# B138B.net
KiCad netlist of a schematic drawn in EAGLE
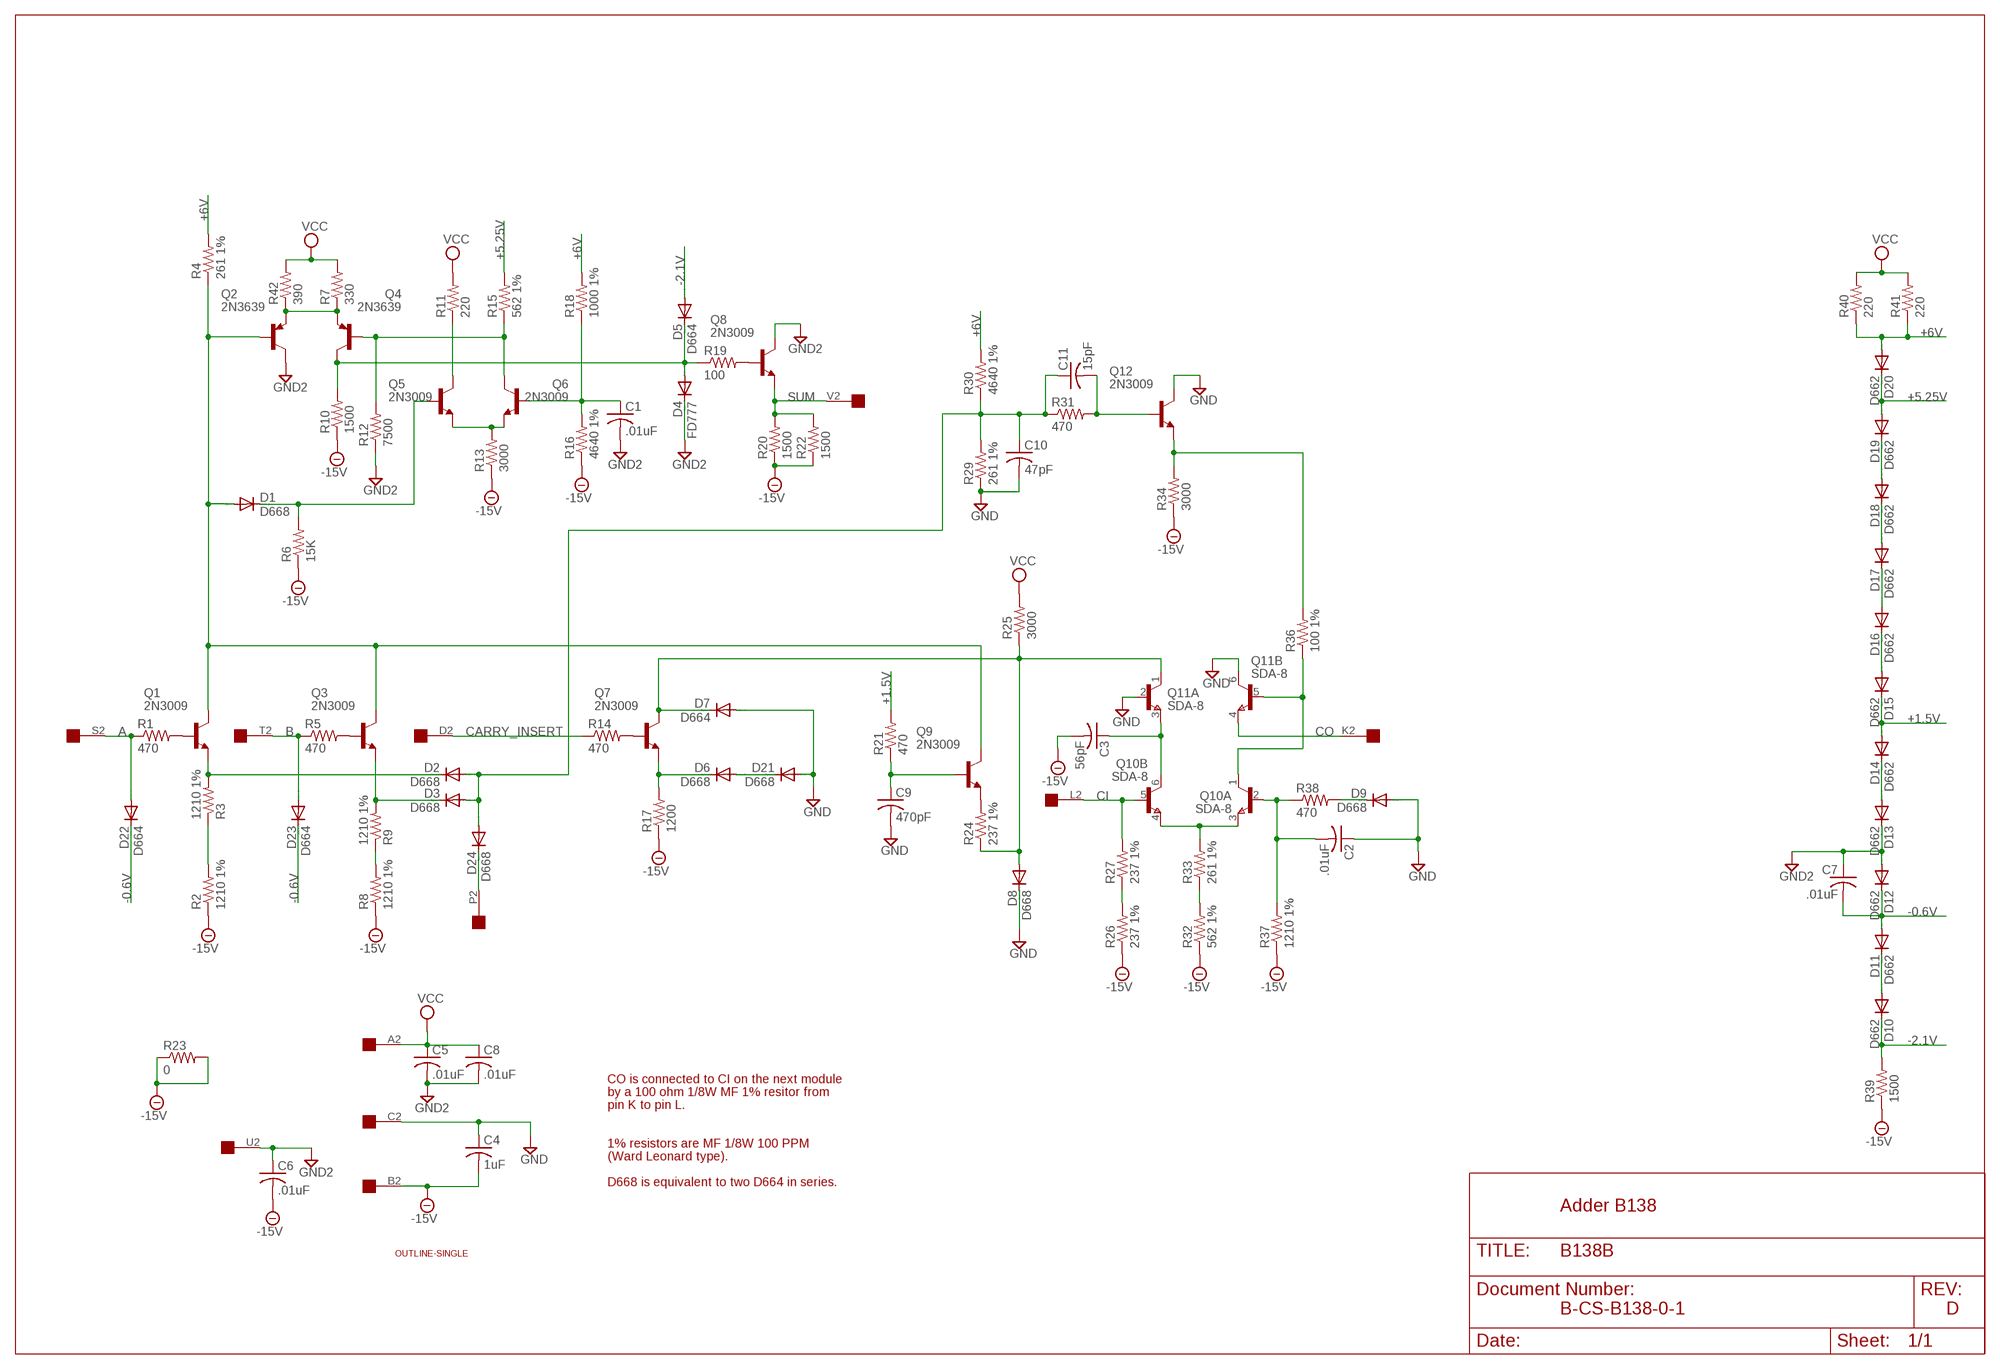
[diagram p0: schematic, sheet 1]

(export (version "E")
  (design (tool "Eeschema 10.0.6"))
  (components
    (comp (ref "C1")
      (value ".01uF")
      (footprint "eagle-import:C063-025X075")
      (libsource (lib "eagle-import") (part "C-US"))
    )
    (comp (ref "C2")
      (value ".01uF")
      (footprint "eagle-import:C063-025X075")
      (libsource (lib "eagle-import") (part "C-US"))
    )
    (comp (ref "C3")
      (value "56pF")
      (footprint "eagle-import:C063-025X075")
      (libsource (lib "eagle-import") (part "C-US"))
    )
    (comp (ref "C4")
      (value "1uF")
      (footprint "eagle-import:C102-043X133")
      (libsource (lib "eagle-import") (part "C-US102-043X133"))
    )
    (comp (ref "C5")
      (value ".01uF")
      (footprint "eagle-import:C063-025X075")
      (libsource (lib "eagle-import") (part "C-US"))
    )
    (comp (ref "C6")
      (value ".01uF")
      (footprint "eagle-import:C063-025X075")
      (libsource (lib "eagle-import") (part "C-US"))
    )
    (comp (ref "C7")
      (value ".01uF")
      (footprint "eagle-import:C063-025X075")
      (libsource (lib "eagle-import") (part "C-US"))
    )
    (comp (ref "C8")
      (value ".01uF")
      (footprint "eagle-import:C063-025X075")
      (libsource (lib "eagle-import") (part "C-US"))
    )
    (comp (ref "C9")
      (value "470pF")
      (footprint "eagle-import:C063-025X075")
      (libsource (lib "eagle-import") (part "C-US"))
    )
    (comp (ref "C10")
      (value "47pF")
      (footprint "eagle-import:C063-025X075")
      (libsource (lib "eagle-import") (part "C-US"))
    )
    (comp (ref "C11")
      (value "15pF")
      (footprint "eagle-import:C063-025X075")
      (libsource (lib "eagle-import") (part "C-US"))
    )
    (comp (ref "D1")
      (value "D668")
      (footprint "eagle-import:DO35-10")
      (libsource (lib "eagle-import") (part "DIODE-DO35-10"))
    )
    (comp (ref "D2")
      (value "D668")
      (footprint "eagle-import:DO35-10")
      (libsource (lib "eagle-import") (part "DIODE-DO35-10"))
    )
    (comp (ref "D3")
      (value "D668")
      (footprint "eagle-import:DO35-10")
      (libsource (lib "eagle-import") (part "DIODE-DO35-10"))
    )
    (comp (ref "D4")
      (value "FD777")
      (footprint "eagle-import:DO35-10")
      (libsource (lib "eagle-import") (part "DIODE-DO35-10"))
    )
    (comp (ref "D5")
      (value "D664")
      (footprint "eagle-import:DO35-10")
      (libsource (lib "eagle-import") (part "DIODE-DO35-10"))
    )
    (comp (ref "D6")
      (value "D668")
      (footprint "eagle-import:DO35-10")
      (libsource (lib "eagle-import") (part "DIODE-DO35-10"))
    )
    (comp (ref "D7")
      (value "D664")
      (footprint "eagle-import:DO35-10")
      (libsource (lib "eagle-import") (part "DIODE-DO35-10"))
    )
    (comp (ref "D8")
      (value "D668")
      (footprint "eagle-import:DO35-10")
      (libsource (lib "eagle-import") (part "DIODE-DO35-10"))
    )
    (comp (ref "D9")
      (value "D668")
      (footprint "eagle-import:DO35-10")
      (libsource (lib "eagle-import") (part "DIODE-DO35-10"))
    )
    (comp (ref "D10")
      (value "D662")
      (footprint "eagle-import:DO35-10")
      (libsource (lib "eagle-import") (part "DIODE-DO35-10"))
    )
    (comp (ref "D11")
      (value "D662")
      (footprint "eagle-import:DO35-10")
      (libsource (lib "eagle-import") (part "DIODE-DO35-10"))
    )
    (comp (ref "D12")
      (value "D662")
      (footprint "eagle-import:DO35-10")
      (libsource (lib "eagle-import") (part "DIODE-DO35-10"))
    )
    (comp (ref "D13")
      (value "D662")
      (footprint "eagle-import:DO35-10")
      (libsource (lib "eagle-import") (part "DIODE-DO35-10"))
    )
    (comp (ref "D14")
      (value "D662")
      (footprint "eagle-import:DO35-10")
      (libsource (lib "eagle-import") (part "DIODE-DO35-10"))
    )
    (comp (ref "D15")
      (value "D662")
      (footprint "eagle-import:DO35-10")
      (libsource (lib "eagle-import") (part "DIODE-DO35-10"))
    )
    (comp (ref "D16")
      (value "D662")
      (footprint "eagle-import:DO35-10")
      (libsource (lib "eagle-import") (part "DIODE-DO35-10"))
    )
    (comp (ref "D17")
      (value "D662")
      (footprint "eagle-import:DO35-10")
      (libsource (lib "eagle-import") (part "DIODE-DO35-10"))
    )
    (comp (ref "D18")
      (value "D662")
      (footprint "eagle-import:DO35-10")
      (libsource (lib "eagle-import") (part "DIODE-DO35-10"))
    )
    (comp (ref "D19")
      (value "D662")
      (footprint "eagle-import:DO35-10")
      (libsource (lib "eagle-import") (part "DIODE-DO35-10"))
    )
    (comp (ref "D20")
      (value "D662")
      (footprint "eagle-import:DO35-10")
      (libsource (lib "eagle-import") (part "DIODE-DO35-10"))
    )
    (comp (ref "D21")
      (value "D668")
      (footprint "eagle-import:DO35-10")
      (libsource (lib "eagle-import") (part "DIODE-DO35-10"))
    )
    (comp (ref "D22")
      (value "D664")
      (footprint "eagle-import:DO35-10")
      (libsource (lib "eagle-import") (part "DIODE-DO35-10"))
    )
    (comp (ref "D23")
      (value "D664")
      (footprint "eagle-import:DO35-10")
      (libsource (lib "eagle-import") (part "DIODE-DO35-10"))
    )
    (comp (ref "D24")
      (value "D668")
      (footprint "eagle-import:DO35-10")
      (libsource (lib "eagle-import") (part "DIODE-DO35-10"))
    )
    (comp (ref "Q1")
      (value "2N3009")
      (footprint "eagle-import:TO5")
      (libsource (lib "eagle-import") (part "-NPN-TO5"))
    )
    (comp (ref "Q2")
      (value "2N3639")
      (footprint "eagle-import:TO5")
      (libsource (lib "eagle-import") (part "-PNP-TO5"))
    )
    (comp (ref "Q3")
      (value "2N3009")
      (footprint "eagle-import:TO5")
      (libsource (lib "eagle-import") (part "-NPN-TO5"))
    )
    (comp (ref "Q4")
      (value "2N3639")
      (footprint "eagle-import:TO5")
      (libsource (lib "eagle-import") (part "-PNP-TO5"))
    )
    (comp (ref "Q5")
      (value "2N3009")
      (footprint "eagle-import:TO5")
      (libsource (lib "eagle-import") (part "-NPN-TO5"))
    )
    (comp (ref "Q6")
      (value "2N3009")
      (footprint "eagle-import:TO5")
      (libsource (lib "eagle-import") (part "-NPN-TO5"))
    )
    (comp (ref "Q7")
      (value "2N3009")
      (footprint "eagle-import:TO5")
      (libsource (lib "eagle-import") (part "-NPN-TO5"))
    )
    (comp (ref "Q8")
      (value "2N3009")
      (footprint "eagle-import:TO5")
      (libsource (lib "eagle-import") (part "-NPN-TO5"))
    )
    (comp (ref "Q9")
      (value "2N3009")
      (footprint "eagle-import:TO5")
      (libsource (lib "eagle-import") (part "-NPN-TO5"))
    )
    (comp (ref "Q10")
      (value "SDA-8")
      (footprint "eagle-import:TO78")
      (libsource (lib "eagle-import") (part "MAT-02H"))
    )
    (comp (ref "Q11")
      (value "SDA-8")
      (footprint "eagle-import:TO78")
      (libsource (lib "eagle-import") (part "MAT-02H"))
    )
    (comp (ref "Q12")
      (value "2N3009")
      (footprint "eagle-import:TO5")
      (libsource (lib "eagle-import") (part "-NPN-TO5"))
    )
    (comp (ref "R1")
      (value "470")
      (footprint "eagle-import:0207_10")
      (libsource (lib "eagle-import") (part "R-US_0207/10"))
    )
    (comp (ref "R2")
      (value "1210 1%")
      (footprint "eagle-import:0207_15")
      (libsource (lib "eagle-import") (part "R-US_0207/15"))
    )
    (comp (ref "R3")
      (value "1210 1%")
      (footprint "eagle-import:0207_15")
      (libsource (lib "eagle-import") (part "R-US_0207/15"))
    )
    (comp (ref "R4")
      (value "261 1%")
      (footprint "eagle-import:0207_15")
      (libsource (lib "eagle-import") (part "R-US_0207/15"))
    )
    (comp (ref "R5")
      (value "470")
      (footprint "eagle-import:0207_10")
      (libsource (lib "eagle-import") (part "R-US_0207/10"))
    )
    (comp (ref "R6")
      (value "15K")
      (footprint "eagle-import:0207_10")
      (libsource (lib "eagle-import") (part "R-US_0207/10"))
    )
    (comp (ref "R7")
      (value "330")
      (footprint "eagle-import:0207_10")
      (libsource (lib "eagle-import") (part "R-US_0207/10"))
    )
    (comp (ref "R8")
      (value "1210 1%")
      (footprint "eagle-import:0207_15")
      (libsource (lib "eagle-import") (part "R-US_0207/15"))
    )
    (comp (ref "R9")
      (value "1210 1%")
      (footprint "eagle-import:0207_15")
      (libsource (lib "eagle-import") (part "R-US_0207/15"))
    )
    (comp (ref "R10")
      (value "1500")
      (footprint "eagle-import:0207_10")
      (libsource (lib "eagle-import") (part "R-US_0207/10"))
    )
    (comp (ref "R11")
      (value "220")
      (footprint "eagle-import:0207_10")
      (libsource (lib "eagle-import") (part "R-US_0207/10"))
    )
    (comp (ref "R12")
      (value "7500")
      (footprint "eagle-import:0207_10")
      (libsource (lib "eagle-import") (part "R-US_0207/10"))
    )
    (comp (ref "R13")
      (value "3000")
      (footprint "eagle-import:0207_10")
      (libsource (lib "eagle-import") (part "R-US_0207/10"))
    )
    (comp (ref "R14")
      (value "470")
      (footprint "eagle-import:0207_10")
      (libsource (lib "eagle-import") (part "R-US_0207/10"))
    )
    (comp (ref "R15")
      (value "562 1%")
      (footprint "eagle-import:0207_15")
      (libsource (lib "eagle-import") (part "R-US_0207/15"))
    )
    (comp (ref "R16")
      (value "4640 1%")
      (footprint "eagle-import:0207_15")
      (libsource (lib "eagle-import") (part "R-US_0207/15"))
    )
    (comp (ref "R17")
      (value "1200")
      (footprint "eagle-import:0207_10")
      (libsource (lib "eagle-import") (part "R-US_0207/10"))
    )
    (comp (ref "R18")
      (value "1000 1%")
      (footprint "eagle-import:0207_15")
      (libsource (lib "eagle-import") (part "R-US_0207/15"))
    )
    (comp (ref "R19")
      (value "100")
      (footprint "eagle-import:0207_10")
      (libsource (lib "eagle-import") (part "R-US_0207/10"))
    )
    (comp (ref "R20")
      (value "1500")
      (footprint "eagle-import:0207_10")
      (libsource (lib "eagle-import") (part "R-US_0207/10"))
    )
    (comp (ref "R21")
      (value "470")
      (footprint "eagle-import:0207_10")
      (libsource (lib "eagle-import") (part "R-US_0207/10"))
    )
    (comp (ref "R22")
      (value "1500")
      (footprint "eagle-import:0207_10")
      (libsource (lib "eagle-import") (part "R-US_0207/10"))
    )
    (comp (ref "R23")
      (value "0")
      (footprint "eagle-import:0207_10")
      (libsource (lib "eagle-import") (part "R-US_0207/10"))
    )
    (comp (ref "R24")
      (value "237 1%")
      (footprint "eagle-import:0207_15")
      (libsource (lib "eagle-import") (part "R-US_0207/15"))
    )
    (comp (ref "R25")
      (value "3000")
      (footprint "eagle-import:0207_10")
      (libsource (lib "eagle-import") (part "R-US_0207/10"))
    )
    (comp (ref "R26")
      (value "237 1%")
      (footprint "eagle-import:0207_15")
      (libsource (lib "eagle-import") (part "R-US_0207/15"))
    )
    (comp (ref "R27")
      (value "237 1%")
      (footprint "eagle-import:0207_15")
      (libsource (lib "eagle-import") (part "R-US_0207/15"))
    )
    (comp (ref "R29")
      (value "261 1%")
      (footprint "eagle-import:0207_15")
      (libsource (lib "eagle-import") (part "R-US_0207/15"))
    )
    (comp (ref "R30")
      (value "4640 1%")
      (footprint "eagle-import:0207_15")
      (libsource (lib "eagle-import") (part "R-US_0207/15"))
    )
    (comp (ref "R31")
      (value "470")
      (footprint "eagle-import:0207_10")
      (libsource (lib "eagle-import") (part "R-US_0207/10"))
    )
    (comp (ref "R32")
      (value "562 1%")
      (footprint "eagle-import:0207_15")
      (libsource (lib "eagle-import") (part "R-US_0207/15"))
    )
    (comp (ref "R33")
      (value "261 1%")
      (footprint "eagle-import:0207_15")
      (libsource (lib "eagle-import") (part "R-US_0207/15"))
    )
    (comp (ref "R34")
      (value "3000")
      (footprint "eagle-import:0207_10")
      (libsource (lib "eagle-import") (part "R-US_0207/10"))
    )
    (comp (ref "R36")
      (value "100 1%")
      (footprint "eagle-import:0207_15")
      (libsource (lib "eagle-import") (part "R-US_0207/15"))
    )
    (comp (ref "R37")
      (value "1210 1%")
      (footprint "eagle-import:0207_15")
      (libsource (lib "eagle-import") (part "R-US_0207/15"))
    )
    (comp (ref "R38")
      (value "470")
      (footprint "eagle-import:0207_10")
      (libsource (lib "eagle-import") (part "R-US_0207/10"))
    )
    (comp (ref "R39")
      (value "1500")
      (footprint "eagle-import:0207_10")
      (libsource (lib "eagle-import") (part "R-US_0207/10"))
    )
    (comp (ref "R40")
      (value "220")
      (footprint "eagle-import:0207_10")
      (libsource (lib "eagle-import") (part "R-US_0207/10"))
    )
    (comp (ref "R41")
      (value "220")
      (footprint "eagle-import:0207_10")
      (libsource (lib "eagle-import") (part "R-US_0207/10"))
    )
    (comp (ref "R42")
      (value "390")
      (footprint "eagle-import:0207_10")
      (libsource (lib "eagle-import") (part "R-US_0207/10"))
    )
    (comp (ref "U$1")
      (value "OUTLINE-SINGLE")
      (footprint "eagle-import:SINGLE")
      (libsource (lib "eagle-import") (part "OUTLINE-SINGLE"))
    )
    (comp (ref "U$2")
      (value "EDGE-1")
      (footprint "eagle-import:EDGE-CON1")
      (libsource (lib "eagle-import") (part "EDGE-1"))
    )
  )
  (nets
    (net (code "1") (name "-15V") (class "Default")
      (node (ref "C3") (pin "2") (pinfunction "2_2") (pintype "passive"))
      (node (ref "C4") (pin "2") (pinfunction "2_2") (pintype "passive"))
      (node (ref "C6") (pin "2") (pinfunction "2_2") (pintype "passive"))
      (node (ref "R10") (pin "1") (pinfunction "1_1") (pintype "passive"))
      (node (ref "R13") (pin "1") (pinfunction "1_1") (pintype "passive"))
      (node (ref "R16") (pin "1") (pinfunction "1_1") (pintype "passive"))
      (node (ref "R17") (pin "1") (pinfunction "1_1") (pintype "passive"))
      (node (ref "R2") (pin "1") (pinfunction "1_1") (pintype "passive"))
      (node (ref "R20") (pin "1") (pinfunction "1_1") (pintype "passive"))
      (node (ref "R22") (pin "1") (pinfunction "1_1") (pintype "passive"))
      (node (ref "R23") (pin "1") (pinfunction "1_1") (pintype "passive"))
      (node (ref "R23") (pin "2") (pinfunction "2_2") (pintype "passive"))
      (node (ref "R26") (pin "1") (pinfunction "1_1") (pintype "passive"))
      (node (ref "R32") (pin "1") (pinfunction "1_1") (pintype "passive"))
      (node (ref "R34") (pin "1") (pinfunction "1_1") (pintype "passive"))
      (node (ref "R37") (pin "1") (pinfunction "1_1") (pintype "passive"))
      (node (ref "R39") (pin "1") (pinfunction "1_1") (pintype "passive"))
      (node (ref "R6") (pin "1") (pinfunction "1_1") (pintype "passive"))
      (node (ref "R8") (pin "1") (pinfunction "1_1") (pintype "passive"))
      (node (ref "U$2") (pin "B2") (pinfunction "1_B2") (pintype "bidirectional"))
    )
    (net (code "2") (name "/+1.5V") (class "Default")
      (node (ref "D14") (pin "A") (pinfunction "A_A") (pintype "passive"))
      (node (ref "D15") (pin "C") (pinfunction "C_C") (pintype "passive"))
      (node (ref "R21") (pin "2") (pinfunction "2_2") (pintype "passive"))
    )
    (net (code "3") (name "/+5.25V") (class "Default")
      (node (ref "D19") (pin "A") (pinfunction "A_A") (pintype "passive"))
      (node (ref "D20") (pin "C") (pinfunction "C_C") (pintype "passive"))
      (node (ref "R15") (pin "2") (pinfunction "2_2") (pintype "passive"))
    )
    (net (code "4") (name "/+6V") (class "Default")
      (node (ref "D20") (pin "A") (pinfunction "A_A") (pintype "passive"))
      (node (ref "R18") (pin "2") (pinfunction "2_2") (pintype "passive"))
      (node (ref "R30") (pin "2") (pinfunction "2_2") (pintype "passive"))
      (node (ref "R4") (pin "2") (pinfunction "2_2") (pintype "passive"))
      (node (ref "R40") (pin "1") (pinfunction "1_1") (pintype "passive"))
      (node (ref "R41") (pin "1") (pinfunction "1_1") (pintype "passive"))
    )
    (net (code "5") (name "/-0.6V") (class "Default")
      (node (ref "C7") (pin "2") (pinfunction "2_2") (pintype "passive"))
      (node (ref "D11") (pin "A") (pinfunction "A_A") (pintype "passive"))
      (node (ref "D12") (pin "C") (pinfunction "C_C") (pintype "passive"))
      (node (ref "D22") (pin "C") (pinfunction "C_C") (pintype "passive"))
      (node (ref "D23") (pin "C") (pinfunction "C_C") (pintype "passive"))
    )
    (net (code "6") (name "/-2.1V") (class "Default")
      (node (ref "D10") (pin "C") (pinfunction "C_C") (pintype "passive"))
      (node (ref "D5") (pin "A") (pinfunction "A_A") (pintype "passive"))
      (node (ref "R39") (pin "2") (pinfunction "2_2") (pintype "passive"))
    )
    (net (code "7") (name "/A") (class "Default")
      (node (ref "D22") (pin "A") (pinfunction "A_A") (pintype "passive"))
      (node (ref "R1") (pin "1") (pinfunction "1_1") (pintype "passive"))
      (node (ref "U$2") (pin "S2") (pinfunction "1_S2") (pintype "bidirectional"))
    )
    (net (code "8") (name "/B") (class "Default")
      (node (ref "D23") (pin "A") (pinfunction "A_A") (pintype "passive"))
      (node (ref "R5") (pin "1") (pinfunction "1_1") (pintype "passive"))
      (node (ref "U$2") (pin "T2") (pinfunction "1_T2") (pintype "bidirectional"))
    )
    (net (code "9") (name "/CARRY_INSERT") (class "Default")
      (node (ref "R14") (pin "1") (pinfunction "1_1") (pintype "passive"))
      (node (ref "U$2") (pin "D2") (pinfunction "1_D2") (pintype "bidirectional"))
    )
    (net (code "10") (name "/CI") (class "Default")
      (node (ref "Q10") (pin "5") (pinfunction "B_5") (pintype "passive"))
      (node (ref "R27") (pin "2") (pinfunction "2_2") (pintype "passive"))
      (node (ref "U$2") (pin "L2") (pinfunction "1_L2") (pintype "bidirectional"))
    )
    (net (code "11") (name "/CO") (class "Default")
      (node (ref "Q11") (pin "4") (pinfunction "E_4") (pintype "passive"))
      (node (ref "U$2") (pin "K2") (pinfunction "1_K2") (pintype "bidirectional"))
    )
    (net (code "12") (name "/SUM") (class "Default")
      (node (ref "Q8") (pin "1") (pinfunction "E_1") (pintype "passive"))
      (node (ref "R20") (pin "2") (pinfunction "2_2") (pintype "passive"))
      (node (ref "R22") (pin "2") (pinfunction "2_2") (pintype "passive"))
      (node (ref "U$2") (pin "V2") (pinfunction "1_V2") (pintype "bidirectional"))
    )
    (net (code "13") (name "GND") (class "Default")
      (node (ref "C10") (pin "2") (pinfunction "2_2") (pintype "passive"))
      (node (ref "C2") (pin "1") (pinfunction "1_1") (pintype "passive"))
      (node (ref "C4") (pin "1") (pinfunction "1_1") (pintype "passive"))
      (node (ref "C9") (pin "2") (pinfunction "2_2") (pintype "passive"))
      (node (ref "D21") (pin "A") (pinfunction "A_A") (pintype "passive"))
      (node (ref "D7") (pin "A") (pinfunction "A_A") (pintype "passive"))
      (node (ref "D8") (pin "C") (pinfunction "C_C") (pintype "passive"))
      (node (ref "D9") (pin "A") (pinfunction "A_A") (pintype "passive"))
      (node (ref "Q11") (pin "2") (pinfunction "B_2") (pintype "passive"))
      (node (ref "Q11") (pin "6") (pinfunction "C_6") (pintype "passive"))
      (node (ref "Q12") (pin "3") (pinfunction "C_3") (pintype "passive"))
      (node (ref "R29") (pin "1") (pinfunction "1_1") (pintype "passive"))
      (node (ref "U$2") (pin "C2") (pinfunction "1_C2") (pintype "bidirectional"))
    )
    (net (code "14") (name "GND2") (class "Default")
      (node (ref "C1") (pin "2") (pinfunction "2_2") (pintype "passive"))
      (node (ref "C5") (pin "2") (pinfunction "2_2") (pintype "passive"))
      (node (ref "C6") (pin "1") (pinfunction "1_1") (pintype "passive"))
      (node (ref "C7") (pin "1") (pinfunction "1_1") (pintype "passive"))
      (node (ref "C8") (pin "2") (pinfunction "2_2") (pintype "passive"))
      (node (ref "D12") (pin "A") (pinfunction "A_A") (pintype "passive"))
      (node (ref "D13") (pin "C") (pinfunction "C_C") (pintype "passive"))
      (node (ref "D4") (pin "C") (pinfunction "C_C") (pintype "passive"))
      (node (ref "Q2") (pin "3") (pinfunction "C_3") (pintype "passive"))
      (node (ref "Q8") (pin "3") (pinfunction "C_3") (pintype "passive"))
      (node (ref "R12") (pin "1") (pinfunction "1_1") (pintype "passive"))
      (node (ref "U$2") (pin "U2") (pinfunction "1_U2") (pintype "bidirectional"))
    )
    (net (code "15") (name "Net-(C10-Pad1)") (class "Default")
      (node (ref "C10") (pin "1") (pinfunction "1_1") (pintype "passive"))
      (node (ref "C11") (pin "1") (pinfunction "1_1") (pintype "passive"))
      (node (ref "D2") (pin "A") (pinfunction "A_A") (pintype "passive"))
      (node (ref "D24") (pin "A") (pinfunction "A_A") (pintype "passive"))
      (node (ref "D3") (pin "A") (pinfunction "A_A") (pintype "passive"))
      (node (ref "R29") (pin "2") (pinfunction "2_2") (pintype "passive"))
      (node (ref "R30") (pin "1") (pinfunction "1_1") (pintype "passive"))
      (node (ref "R31") (pin "1") (pinfunction "1_1") (pintype "passive"))
    )
    (net (code "16") (name "Net-(D9-PadC)") (class "Default")
      (node (ref "D9") (pin "C") (pinfunction "C_C") (pintype "passive"))
      (node (ref "R38") (pin "2") (pinfunction "2_2") (pintype "passive"))
    )
    (net (code "17") (name "Net-(D10-PadA)") (class "Default")
      (node (ref "D10") (pin "A") (pinfunction "A_A") (pintype "passive"))
      (node (ref "D11") (pin "C") (pinfunction "C_C") (pintype "passive"))
    )
    (net (code "18") (name "Net-(D13-PadA)") (class "Default")
      (node (ref "D13") (pin "A") (pinfunction "A_A") (pintype "passive"))
      (node (ref "D14") (pin "C") (pinfunction "C_C") (pintype "passive"))
    )
    (net (code "19") (name "Net-(D15-PadA)") (class "Default")
      (node (ref "D15") (pin "A") (pinfunction "A_A") (pintype "passive"))
      (node (ref "D16") (pin "C") (pinfunction "C_C") (pintype "passive"))
    )
    (net (code "20") (name "Net-(D16-PadA)") (class "Default")
      (node (ref "D16") (pin "A") (pinfunction "A_A") (pintype "passive"))
      (node (ref "D17") (pin "C") (pinfunction "C_C") (pintype "passive"))
    )
    (net (code "21") (name "Net-(D17-PadA)") (class "Default")
      (node (ref "D17") (pin "A") (pinfunction "A_A") (pintype "passive"))
      (node (ref "D18") (pin "C") (pinfunction "C_C") (pintype "passive"))
    )
    (net (code "22") (name "Net-(D18-PadA)") (class "Default")
      (node (ref "D18") (pin "A") (pinfunction "A_A") (pintype "passive"))
      (node (ref "D19") (pin "C") (pinfunction "C_C") (pintype "passive"))
    )
    (net (code "23") (name "Net-(D21-PadC)") (class "Default")
      (node (ref "D21") (pin "C") (pinfunction "C_C") (pintype "passive"))
      (node (ref "D6") (pin "A") (pinfunction "A_A") (pintype "passive"))
    )
    (net (code "24") (name "Net-(Q1-B)") (class "Default")
      (node (ref "Q1") (pin "2") (pinfunction "B_2") (pintype "passive"))
      (node (ref "R1") (pin "2") (pinfunction "2_2") (pintype "passive"))
    )
    (net (code "25") (name "Net-(Q1-C)") (class "Default")
      (node (ref "D1") (pin "A") (pinfunction "A_A") (pintype "passive"))
      (node (ref "Q1") (pin "3") (pinfunction "C_3") (pintype "passive"))
      (node (ref "Q2") (pin "2") (pinfunction "B_2") (pintype "passive"))
      (node (ref "Q3") (pin "3") (pinfunction "C_3") (pintype "passive"))
      (node (ref "Q9") (pin "3") (pinfunction "C_3") (pintype "passive"))
      (node (ref "R4") (pin "1") (pinfunction "1_1") (pintype "passive"))
    )
    (net (code "26") (name "Net-(Q1-E)") (class "Default")
      (node (ref "D2") (pin "C") (pinfunction "C_C") (pintype "passive"))
      (node (ref "Q1") (pin "1") (pinfunction "E_1") (pintype "passive"))
      (node (ref "R3") (pin "2") (pinfunction "2_2") (pintype "passive"))
    )
    (net (code "27") (name "Net-(Q2-E)") (class "Default")
      (node (ref "Q2") (pin "1") (pinfunction "E_1") (pintype "passive"))
      (node (ref "Q4") (pin "1") (pinfunction "E_1") (pintype "passive"))
      (node (ref "R42") (pin "1") (pinfunction "1_1") (pintype "passive"))
      (node (ref "R7") (pin "1") (pinfunction "1_1") (pintype "passive"))
    )
    (net (code "28") (name "Net-(Q3-B)") (class "Default")
      (node (ref "Q3") (pin "2") (pinfunction "B_2") (pintype "passive"))
      (node (ref "R5") (pin "2") (pinfunction "2_2") (pintype "passive"))
    )
    (net (code "29") (name "Net-(Q3-E)") (class "Default")
      (node (ref "D3") (pin "C") (pinfunction "C_C") (pintype "passive"))
      (node (ref "Q3") (pin "1") (pinfunction "E_1") (pintype "passive"))
      (node (ref "R9") (pin "2") (pinfunction "2_2") (pintype "passive"))
    )
    (net (code "30") (name "Net-(Q4-B)") (class "Default")
      (node (ref "Q4") (pin "2") (pinfunction "B_2") (pintype "passive"))
      (node (ref "Q6") (pin "3") (pinfunction "C_3") (pintype "passive"))
      (node (ref "R12") (pin "2") (pinfunction "2_2") (pintype "passive"))
      (node (ref "R15") (pin "1") (pinfunction "1_1") (pintype "passive"))
    )
    (net (code "31") (name "Net-(Q4-C)") (class "Default")
      (node (ref "D4") (pin "A") (pinfunction "A_A") (pintype "passive"))
      (node (ref "D5") (pin "C") (pinfunction "C_C") (pintype "passive"))
      (node (ref "Q4") (pin "3") (pinfunction "C_3") (pintype "passive"))
      (node (ref "R10") (pin "2") (pinfunction "2_2") (pintype "passive"))
      (node (ref "R19") (pin "1") (pinfunction "1_1") (pintype "passive"))
    )
    (net (code "32") (name "Net-(Q5-B)") (class "Default")
      (node (ref "D1") (pin "C") (pinfunction "C_C") (pintype "passive"))
      (node (ref "Q5") (pin "2") (pinfunction "B_2") (pintype "passive"))
      (node (ref "R6") (pin "2") (pinfunction "2_2") (pintype "passive"))
    )
    (net (code "33") (name "Net-(Q5-C)") (class "Default")
      (node (ref "Q5") (pin "3") (pinfunction "C_3") (pintype "passive"))
      (node (ref "R11") (pin "1") (pinfunction "1_1") (pintype "passive"))
    )
    (net (code "34") (name "Net-(Q5-E)") (class "Default")
      (node (ref "Q5") (pin "1") (pinfunction "E_1") (pintype "passive"))
      (node (ref "Q6") (pin "1") (pinfunction "E_1") (pintype "passive"))
      (node (ref "R13") (pin "2") (pinfunction "2_2") (pintype "passive"))
    )
    (net (code "35") (name "Net-(Q6-B)") (class "Default")
      (node (ref "C1") (pin "1") (pinfunction "1_1") (pintype "passive"))
      (node (ref "Q6") (pin "2") (pinfunction "B_2") (pintype "passive"))
      (node (ref "R16") (pin "2") (pinfunction "2_2") (pintype "passive"))
      (node (ref "R18") (pin "1") (pinfunction "1_1") (pintype "passive"))
    )
    (net (code "36") (name "Net-(Q7-B)") (class "Default")
      (node (ref "Q7") (pin "2") (pinfunction "B_2") (pintype "passive"))
      (node (ref "R14") (pin "2") (pinfunction "2_2") (pintype "passive"))
    )
    (net (code "37") (name "Net-(Q7-E)") (class "Default")
      (node (ref "D6") (pin "C") (pinfunction "C_C") (pintype "passive"))
      (node (ref "Q7") (pin "1") (pinfunction "E_1") (pintype "passive"))
      (node (ref "R17") (pin "2") (pinfunction "2_2") (pintype "passive"))
    )
    (net (code "38") (name "Net-(Q8-B)") (class "Default")
      (node (ref "Q8") (pin "2") (pinfunction "B_2") (pintype "passive"))
      (node (ref "R19") (pin "2") (pinfunction "2_2") (pintype "passive"))
    )
    (net (code "39") (name "Net-(Q9-B)") (class "Default")
      (node (ref "C9") (pin "1") (pinfunction "1_1") (pintype "passive"))
      (node (ref "Q9") (pin "2") (pinfunction "B_2") (pintype "passive"))
      (node (ref "R21") (pin "1") (pinfunction "1_1") (pintype "passive"))
    )
    (net (code "40") (name "Net-(Q9-E)") (class "Default")
      (node (ref "Q9") (pin "1") (pinfunction "E_1") (pintype "passive"))
      (node (ref "R24") (pin "2") (pinfunction "2_2") (pintype "passive"))
    )
    (net (code "41") (name "Net-(Q10A-B)") (class "Default")
      (node (ref "C2") (pin "2") (pinfunction "2_2") (pintype "passive"))
      (node (ref "Q10") (pin "2") (pinfunction "B_2") (pintype "passive"))
      (node (ref "R37") (pin "2") (pinfunction "2_2") (pintype "passive"))
      (node (ref "R38") (pin "1") (pinfunction "1_1") (pintype "passive"))
    )
    (net (code "42") (name "Net-(Q10A-C)") (class "Default")
      (node (ref "Q10") (pin "1") (pinfunction "C_1") (pintype "passive"))
      (node (ref "Q11") (pin "5") (pinfunction "B_5") (pintype "passive"))
      (node (ref "R36") (pin "1") (pinfunction "1_1") (pintype "passive"))
    )
    (net (code "43") (name "Net-(Q10A-E)") (class "Default")
      (node (ref "Q10") (pin "3") (pinfunction "E_3") (pintype "passive"))
      (node (ref "Q10") (pin "4") (pinfunction "E_4") (pintype "passive"))
      (node (ref "R33") (pin "2") (pinfunction "2_2") (pintype "passive"))
    )
    (net (code "44") (name "Net-(Q10B-C)") (class "Default")
      (node (ref "C3") (pin "1") (pinfunction "1_1") (pintype "passive"))
      (node (ref "Q10") (pin "6") (pinfunction "C_6") (pintype "passive"))
      (node (ref "Q11") (pin "3") (pinfunction "E_3") (pintype "passive"))
    )
    (net (code "45") (name "Net-(Q11A-C)") (class "Default")
      (node (ref "D7") (pin "C") (pinfunction "C_C") (pintype "passive"))
      (node (ref "D8") (pin "A") (pinfunction "A_A") (pintype "passive"))
      (node (ref "Q11") (pin "1") (pinfunction "C_1") (pintype "passive"))
      (node (ref "Q7") (pin "3") (pinfunction "C_3") (pintype "passive"))
      (node (ref "R24") (pin "1") (pinfunction "1_1") (pintype "passive"))
      (node (ref "R25") (pin "1") (pinfunction "1_1") (pintype "passive"))
    )
    (net (code "46") (name "Net-(Q12-B)") (class "Default")
      (node (ref "C11") (pin "2") (pinfunction "2_2") (pintype "passive"))
      (node (ref "Q12") (pin "2") (pinfunction "B_2") (pintype "passive"))
      (node (ref "R31") (pin "2") (pinfunction "2_2") (pintype "passive"))
    )
    (net (code "47") (name "Net-(Q12-E)") (class "Default")
      (node (ref "Q12") (pin "1") (pinfunction "E_1") (pintype "passive"))
      (node (ref "R34") (pin "2") (pinfunction "2_2") (pintype "passive"))
      (node (ref "R36") (pin "2") (pinfunction "2_2") (pintype "passive"))
    )
    (net (code "48") (name "Net-(R2-Pad2)") (class "Default")
      (node (ref "R2") (pin "2") (pinfunction "2_2") (pintype "passive"))
      (node (ref "R3") (pin "1") (pinfunction "1_1") (pintype "passive"))
    )
    (net (code "49") (name "Net-(R8-Pad2)") (class "Default")
      (node (ref "R8") (pin "2") (pinfunction "2_2") (pintype "passive"))
      (node (ref "R9") (pin "1") (pinfunction "1_1") (pintype "passive"))
    )
    (net (code "50") (name "Net-(R26-Pad2)") (class "Default")
      (node (ref "R26") (pin "2") (pinfunction "2_2") (pintype "passive"))
      (node (ref "R27") (pin "1") (pinfunction "1_1") (pintype "passive"))
    )
    (net (code "51") (name "Net-(R32-Pad2)") (class "Default")
      (node (ref "R32") (pin "2") (pinfunction "2_2") (pintype "passive"))
      (node (ref "R33") (pin "1") (pinfunction "1_1") (pintype "passive"))
    )
    (net (code "52") (name "Net-(U$2M-1)") (class "Default")
      (node (ref "D24") (pin "C") (pinfunction "C_C") (pintype "passive"))
      (node (ref "U$2") (pin "P2") (pinfunction "1_P2") (pintype "bidirectional"))
    )
    (net (code "53") (name "VCC") (class "Default")
      (node (ref "C5") (pin "1") (pinfunction "1_1") (pintype "passive"))
      (node (ref "C8") (pin "1") (pinfunction "1_1") (pintype "passive"))
      (node (ref "R11") (pin "2") (pinfunction "2_2") (pintype "passive"))
      (node (ref "R25") (pin "2") (pinfunction "2_2") (pintype "passive"))
      (node (ref "R40") (pin "2") (pinfunction "2_2") (pintype "passive"))
      (node (ref "R41") (pin "2") (pinfunction "2_2") (pintype "passive"))
      (node (ref "R42") (pin "2") (pinfunction "2_2") (pintype "passive"))
      (node (ref "R7") (pin "2") (pinfunction "2_2") (pintype "passive"))
      (node (ref "U$2") (pin "A2") (pinfunction "1_A2") (pintype "bidirectional"))
    )
  )
)
